# SCH_Piano_12_keys_2022-07-06.net
KiCad netlist of a schematic drawn in EasyEDA
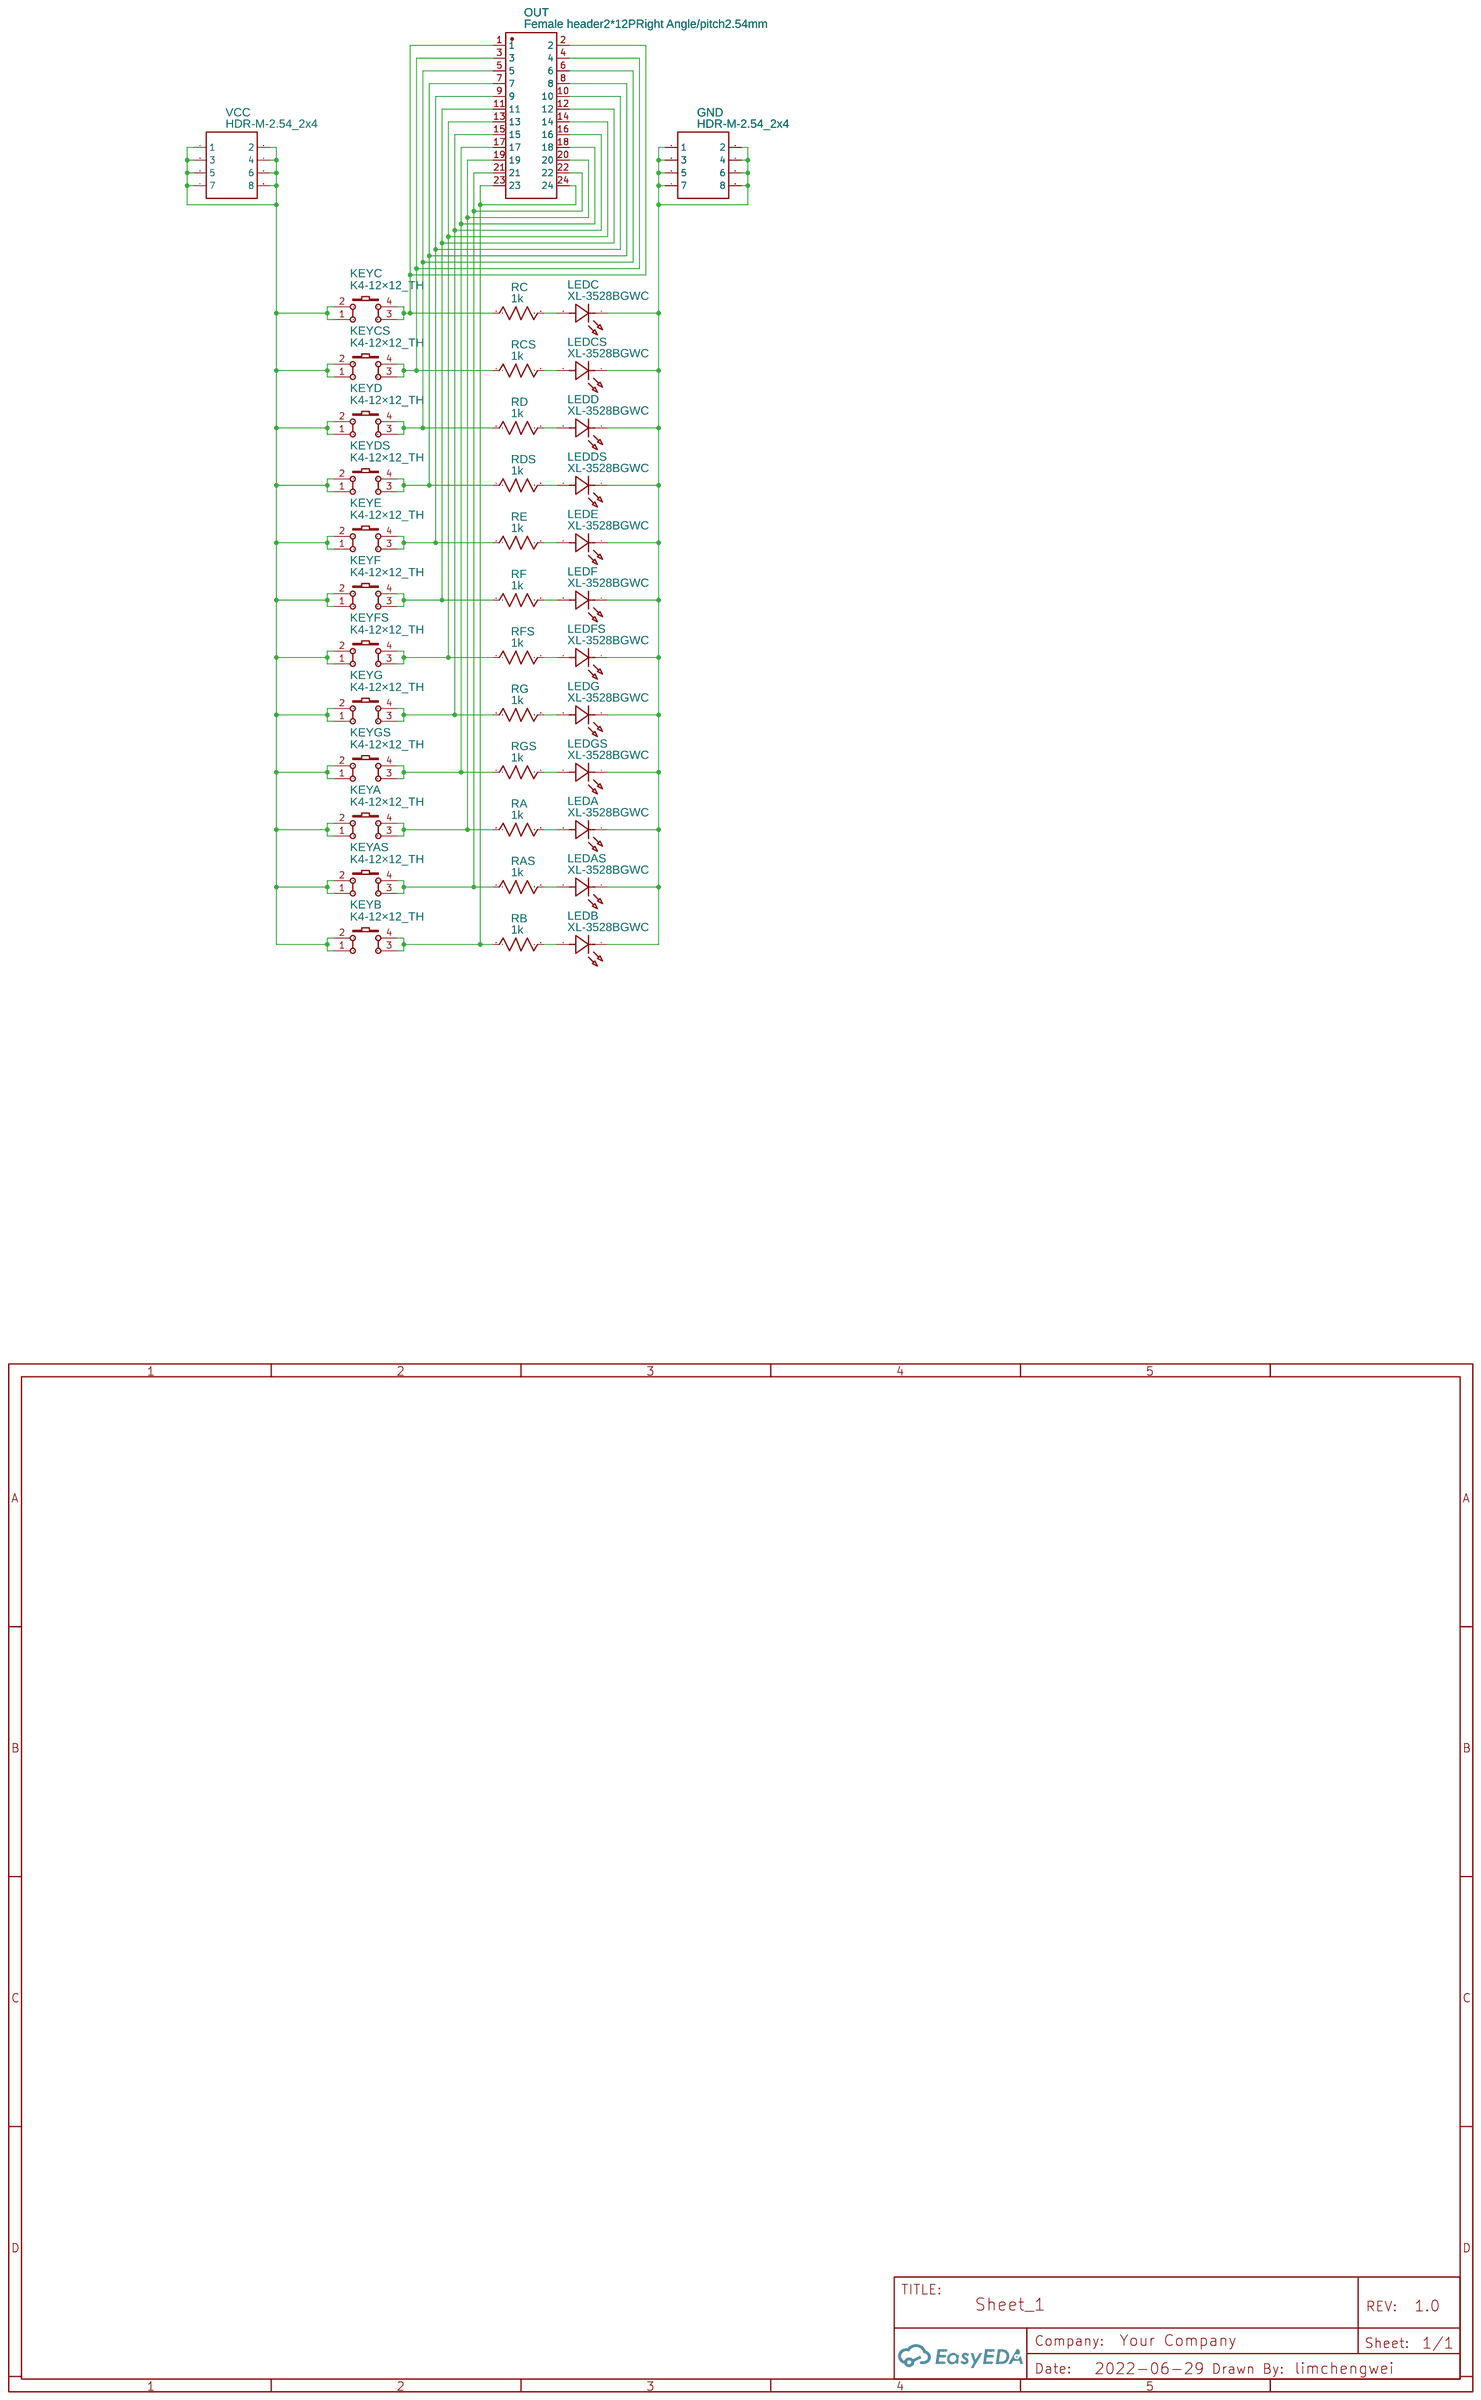
[diagram p0: schematic sheet]

(export (version "E")
  (design (tool "Eeschema 10.0.6"))
  (components
    (comp (ref "GND")
      (value "HDR-M-2.54_2x4")
      (fields (field (name "BOM_Supplier Part") "C58363"))
      (libsource (lib "") (part "HDR-M-2.54_2x4"))
    )
    (comp (ref "KEYA")
      (value "K4-12×12_TH")
      (fields
        (field (name "BOM_Manufacturer Part") "K2-1103DP-M4SW-04")
        (field (name "BOM_Supplier Part") "C128053")
      )
      (libsource (lib "") (part "K4-12×12_TH_9"))
    )
    (comp (ref "KEYAS")
      (value "K4-12×12_TH")
      (fields
        (field (name "BOM_Manufacturer Part") "K2-1103DP-M4SW-04")
        (field (name "BOM_Supplier Part") "C128053")
      )
      (libsource (lib "") (part "K4-12×12_TH_10"))
    )
    (comp (ref "KEYB")
      (value "K4-12×12_TH")
      (fields
        (field (name "BOM_Manufacturer Part") "K2-1103DP-M4SW-04")
        (field (name "BOM_Supplier Part") "C128053")
      )
      (libsource (lib "") (part "K4-12×12_TH_4"))
    )
    (comp (ref "KEYC")
      (value "K4-12×12_TH")
      (fields
        (field (name "BOM_Manufacturer Part") "K2-1103DP-M4SW-04")
        (field (name "BOM_Supplier Part") "C128053")
      )
      (libsource (lib "") (part "K4-12×12_TH_3"))
    )
    (comp (ref "KEYCS")
      (value "K4-12×12_TH")
      (fields
        (field (name "BOM_Manufacturer Part") "K2-1103DP-M4SW-04")
        (field (name "BOM_Supplier Part") "C128053")
      )
      (libsource (lib "") (part "K4-12×12_TH"))
    )
    (comp (ref "KEYD")
      (value "K4-12×12_TH")
      (fields
        (field (name "BOM_Manufacturer Part") "K2-1103DP-M4SW-04")
        (field (name "BOM_Supplier Part") "C128053")
      )
      (libsource (lib "") (part "K4-12×12_TH_8"))
    )
    (comp (ref "KEYDS")
      (value "K4-12×12_TH")
      (fields
        (field (name "BOM_Manufacturer Part") "K2-1103DP-M4SW-04")
        (field (name "BOM_Supplier Part") "C128053")
      )
      (libsource (lib "") (part "K4-12×12_TH_1"))
    )
    (comp (ref "KEYE")
      (value "K4-12×12_TH")
      (fields
        (field (name "BOM_Manufacturer Part") "K2-1103DP-M4SW-04")
        (field (name "BOM_Supplier Part") "C128053")
      )
      (libsource (lib "") (part "K4-12×12_TH_11"))
    )
    (comp (ref "KEYF")
      (value "K4-12×12_TH")
      (fields
        (field (name "BOM_Manufacturer Part") "K2-1103DP-M4SW-04")
        (field (name "BOM_Supplier Part") "C128053")
      )
      (libsource (lib "") (part "K4-12×12_TH_6"))
    )
    (comp (ref "KEYFS")
      (value "K4-12×12_TH")
      (fields
        (field (name "BOM_Manufacturer Part") "K2-1103DP-M4SW-04")
        (field (name "BOM_Supplier Part") "C128053")
      )
      (libsource (lib "") (part "K4-12×12_TH_2"))
    )
    (comp (ref "KEYG")
      (value "K4-12×12_TH")
      (fields
        (field (name "BOM_Manufacturer Part") "K2-1103DP-M4SW-04")
        (field (name "BOM_Supplier Part") "C128053")
      )
      (libsource (lib "") (part "K4-12×12_TH_7"))
    )
    (comp (ref "KEYGS")
      (value "K4-12×12_TH")
      (fields
        (field (name "BOM_Manufacturer Part") "K2-1103DP-M4SW-04")
        (field (name "BOM_Supplier Part") "C128053")
      )
      (libsource (lib "") (part "K4-12×12_TH_5"))
    )
    (comp (ref "LEDA")
      (value "XL-3528BGWC")
      (fields (field (name "BOM_Supplier Part") "C2843807"))
      (libsource (lib "") (part "XL-3528BGWC_7"))
    )
    (comp (ref "LEDAS")
      (value "XL-3528BGWC")
      (fields (field (name "BOM_Supplier Part") "C2843807"))
      (libsource (lib "") (part "XL-3528BGWC_1"))
    )
    (comp (ref "LEDB")
      (value "XL-3528BGWC")
      (fields (field (name "BOM_Supplier Part") "C2843807"))
      (libsource (lib "") (part "XL-3528BGWC"))
    )
    (comp (ref "LEDC")
      (value "XL-3528BGWC")
      (fields (field (name "BOM_Supplier Part") "C2843807"))
      (libsource (lib "") (part "XL-3528BGWC_5"))
    )
    (comp (ref "LEDCS")
      (value "XL-3528BGWC")
      (fields (field (name "BOM_Supplier Part") "C2843807"))
      (libsource (lib "") (part "XL-3528BGWC_11"))
    )
    (comp (ref "LEDD")
      (value "XL-3528BGWC")
      (fields (field (name "BOM_Supplier Part") "C2843807"))
      (libsource (lib "") (part "XL-3528BGWC_8"))
    )
    (comp (ref "LEDDS")
      (value "XL-3528BGWC")
      (fields (field (name "BOM_Supplier Part") "C2843807"))
      (libsource (lib "") (part "XL-3528BGWC_9"))
    )
    (comp (ref "LEDE")
      (value "XL-3528BGWC")
      (fields (field (name "BOM_Supplier Part") "C2843807"))
      (libsource (lib "") (part "XL-3528BGWC_2"))
    )
    (comp (ref "LEDF")
      (value "XL-3528BGWC")
      (fields (field (name "BOM_Supplier Part") "C2843807"))
      (libsource (lib "") (part "XL-3528BGWC_6"))
    )
    (comp (ref "LEDFS")
      (value "XL-3528BGWC")
      (fields (field (name "BOM_Supplier Part") "C2843807"))
      (libsource (lib "") (part "XL-3528BGWC_4"))
    )
    (comp (ref "LEDG")
      (value "XL-3528BGWC")
      (fields (field (name "BOM_Supplier Part") "C2843807"))
      (libsource (lib "") (part "XL-3528BGWC_3"))
    )
    (comp (ref "LEDGS")
      (value "XL-3528BGWC")
      (fields (field (name "BOM_Supplier Part") "C2843807"))
      (libsource (lib "") (part "XL-3528BGWC_10"))
    )
    (comp (ref "OUT")
      (value "Female header2*12PRight Angle/pitch2.54mm")
      (fields (field (name "BOM_Supplier Part") "C62744"))
      (libsource (lib "") (part "Female header2*12PRight Angle/pitch2.54mm"))
    )
    (comp (ref "RA") (value "1k") (libsource (lib "") (part "R_1206_US_8")))
    (comp (ref "RAS") (value "1k") (libsource (lib "") (part "R_1206_US_6")))
    (comp (ref "RB") (value "1k") (libsource (lib "") (part "R_1206_US_4")))
    (comp (ref "RC") (value "1k") (libsource (lib "") (part "R_1206_US_3")))
    (comp (ref "RCS") (value "1k") (libsource (lib "") (part "R_1206_US_1")))
    (comp (ref "RD") (value "1k") (libsource (lib "") (part "R_1206_US_2")))
    (comp (ref "RDS") (value "1k") (libsource (lib "") (part "R_1206_US_9")))
    (comp (ref "RE") (value "1k") (libsource (lib "") (part "R_1206_US_11")))
    (comp (ref "RF") (value "1k") (libsource (lib "") (part "R_1206_US")))
    (comp (ref "RFS") (value "1k") (libsource (lib "") (part "R_1206_US_5")))
    (comp (ref "RG") (value "1k") (libsource (lib "") (part "R_1206_US_10")))
    (comp (ref "RGS") (value "1k") (libsource (lib "") (part "R_1206_US_7")))
    (comp (ref "VCC")
      (value "HDR-M-2.54_2x4")
      (fields (field (name "BOM_Supplier Part") "C58363"))
      (libsource (lib "") (part "HDR-M-2.54_2x4_1"))
    )
  )
  (nets
    (net (code "1") (name "Net-(KEYA-Pad1)") (class "Default")
      (node (ref "KEYA") (pin "1") (pinfunction "1_1") (pintype "unspecified"))
      (node (ref "KEYA") (pin "2") (pinfunction "2_2") (pintype "unspecified"))
      (node (ref "KEYAS") (pin "1") (pinfunction "1_1") (pintype "unspecified"))
      (node (ref "KEYAS") (pin "2") (pinfunction "2_2") (pintype "unspecified"))
      (node (ref "KEYB") (pin "1") (pinfunction "1_1") (pintype "unspecified"))
      (node (ref "KEYB") (pin "2") (pinfunction "2_2") (pintype "unspecified"))
      (node (ref "KEYC") (pin "1") (pinfunction "1_1") (pintype "unspecified"))
      (node (ref "KEYC") (pin "2") (pinfunction "2_2") (pintype "unspecified"))
      (node (ref "KEYCS") (pin "1") (pinfunction "1_1") (pintype "unspecified"))
      (node (ref "KEYCS") (pin "2") (pinfunction "2_2") (pintype "unspecified"))
      (node (ref "KEYD") (pin "1") (pinfunction "1_1") (pintype "unspecified"))
      (node (ref "KEYD") (pin "2") (pinfunction "2_2") (pintype "unspecified"))
      (node (ref "KEYDS") (pin "1") (pinfunction "1_1") (pintype "unspecified"))
      (node (ref "KEYDS") (pin "2") (pinfunction "2_2") (pintype "unspecified"))
      (node (ref "KEYE") (pin "1") (pinfunction "1_1") (pintype "unspecified"))
      (node (ref "KEYE") (pin "2") (pinfunction "2_2") (pintype "unspecified"))
      (node (ref "KEYF") (pin "1") (pinfunction "1_1") (pintype "unspecified"))
      (node (ref "KEYF") (pin "2") (pinfunction "2_2") (pintype "unspecified"))
      (node (ref "KEYFS") (pin "1") (pinfunction "1_1") (pintype "unspecified"))
      (node (ref "KEYFS") (pin "2") (pinfunction "2_2") (pintype "unspecified"))
      (node (ref "KEYG") (pin "1") (pinfunction "1_1") (pintype "unspecified"))
      (node (ref "KEYG") (pin "2") (pinfunction "2_2") (pintype "unspecified"))
      (node (ref "KEYGS") (pin "1") (pinfunction "1_1") (pintype "unspecified"))
      (node (ref "KEYGS") (pin "2") (pinfunction "2_2") (pintype "unspecified"))
      (node (ref "VCC") (pin "1") (pinfunction "1_1") (pintype "unspecified"))
      (node (ref "VCC") (pin "2") (pinfunction "2_2") (pintype "unspecified"))
      (node (ref "VCC") (pin "3") (pinfunction "3_3") (pintype "unspecified"))
      (node (ref "VCC") (pin "4") (pinfunction "4_4") (pintype "unspecified"))
      (node (ref "VCC") (pin "5") (pinfunction "5_5") (pintype "unspecified"))
      (node (ref "VCC") (pin "6") (pinfunction "6_6") (pintype "unspecified"))
      (node (ref "VCC") (pin "7") (pinfunction "7_7") (pintype "unspecified"))
      (node (ref "VCC") (pin "8") (pinfunction "8_8") (pintype "unspecified"))
    )
    (net (code "2") (name "Net-(KEYA-Pad3)") (class "Default")
      (node (ref "KEYA") (pin "3") (pinfunction "3_3") (pintype "unspecified"))
      (node (ref "KEYA") (pin "4") (pinfunction "4_4") (pintype "unspecified"))
      (node (ref "OUT") (pin "19") (pinfunction "19_19") (pintype "unspecified"))
      (node (ref "OUT") (pin "20") (pinfunction "20_20") (pintype "unspecified"))
      (node (ref "RA") (pin "1") (pinfunction "1_1") (pintype "unspecified"))
    )
    (net (code "3") (name "Net-(KEYAS-Pad3)") (class "Default")
      (node (ref "KEYAS") (pin "3") (pinfunction "3_3") (pintype "unspecified"))
      (node (ref "KEYAS") (pin "4") (pinfunction "4_4") (pintype "unspecified"))
      (node (ref "OUT") (pin "21") (pinfunction "21_21") (pintype "unspecified"))
      (node (ref "OUT") (pin "22") (pinfunction "22_22") (pintype "unspecified"))
      (node (ref "RAS") (pin "1") (pinfunction "1_1") (pintype "unspecified"))
    )
    (net (code "4") (name "Net-(KEYB-Pad3)") (class "Default")
      (node (ref "KEYB") (pin "3") (pinfunction "3_3") (pintype "unspecified"))
      (node (ref "KEYB") (pin "4") (pinfunction "4_4") (pintype "unspecified"))
      (node (ref "OUT") (pin "23") (pinfunction "23_23") (pintype "unspecified"))
      (node (ref "OUT") (pin "24") (pinfunction "24_24") (pintype "unspecified"))
      (node (ref "RB") (pin "1") (pinfunction "1_1") (pintype "unspecified"))
    )
    (net (code "5") (name "Net-(KEYC-Pad3)") (class "Default")
      (node (ref "KEYC") (pin "3") (pinfunction "3_3") (pintype "unspecified"))
      (node (ref "KEYC") (pin "4") (pinfunction "4_4") (pintype "unspecified"))
      (node (ref "OUT") (pin "1") (pinfunction "1_1") (pintype "unspecified"))
      (node (ref "OUT") (pin "2") (pinfunction "2_2") (pintype "unspecified"))
      (node (ref "RC") (pin "1") (pinfunction "1_1") (pintype "unspecified"))
    )
    (net (code "6") (name "Net-(KEYCS-Pad3)") (class "Default")
      (node (ref "KEYCS") (pin "3") (pinfunction "3_3") (pintype "unspecified"))
      (node (ref "KEYCS") (pin "4") (pinfunction "4_4") (pintype "unspecified"))
      (node (ref "OUT") (pin "3") (pinfunction "3_3") (pintype "unspecified"))
      (node (ref "OUT") (pin "4") (pinfunction "4_4") (pintype "unspecified"))
      (node (ref "RCS") (pin "1") (pinfunction "1_1") (pintype "unspecified"))
    )
    (net (code "7") (name "Net-(KEYD-Pad3)") (class "Default")
      (node (ref "KEYD") (pin "3") (pinfunction "3_3") (pintype "unspecified"))
      (node (ref "KEYD") (pin "4") (pinfunction "4_4") (pintype "unspecified"))
      (node (ref "OUT") (pin "5") (pinfunction "5_5") (pintype "unspecified"))
      (node (ref "OUT") (pin "6") (pinfunction "6_6") (pintype "unspecified"))
      (node (ref "RD") (pin "1") (pinfunction "1_1") (pintype "unspecified"))
    )
    (net (code "8") (name "Net-(KEYDS-Pad3)") (class "Default")
      (node (ref "KEYDS") (pin "3") (pinfunction "3_3") (pintype "unspecified"))
      (node (ref "KEYDS") (pin "4") (pinfunction "4_4") (pintype "unspecified"))
      (node (ref "OUT") (pin "7") (pinfunction "7_7") (pintype "unspecified"))
      (node (ref "OUT") (pin "8") (pinfunction "8_8") (pintype "unspecified"))
      (node (ref "RDS") (pin "1") (pinfunction "1_1") (pintype "unspecified"))
    )
    (net (code "9") (name "Net-(KEYE-Pad3)") (class "Default")
      (node (ref "KEYE") (pin "3") (pinfunction "3_3") (pintype "unspecified"))
      (node (ref "KEYE") (pin "4") (pinfunction "4_4") (pintype "unspecified"))
      (node (ref "OUT") (pin "10") (pinfunction "10_10") (pintype "unspecified"))
      (node (ref "OUT") (pin "9") (pinfunction "9_9") (pintype "unspecified"))
      (node (ref "RE") (pin "1") (pinfunction "1_1") (pintype "unspecified"))
    )
    (net (code "10") (name "Net-(KEYF-Pad3)") (class "Default")
      (node (ref "KEYF") (pin "3") (pinfunction "3_3") (pintype "unspecified"))
      (node (ref "KEYF") (pin "4") (pinfunction "4_4") (pintype "unspecified"))
      (node (ref "OUT") (pin "11") (pinfunction "11_11") (pintype "unspecified"))
      (node (ref "OUT") (pin "12") (pinfunction "12_12") (pintype "unspecified"))
      (node (ref "RF") (pin "1") (pinfunction "1_1") (pintype "unspecified"))
    )
    (net (code "11") (name "Net-(KEYFS-Pad3)") (class "Default")
      (node (ref "KEYFS") (pin "3") (pinfunction "3_3") (pintype "unspecified"))
      (node (ref "KEYFS") (pin "4") (pinfunction "4_4") (pintype "unspecified"))
      (node (ref "OUT") (pin "13") (pinfunction "13_13") (pintype "unspecified"))
      (node (ref "OUT") (pin "14") (pinfunction "14_14") (pintype "unspecified"))
      (node (ref "RFS") (pin "1") (pinfunction "1_1") (pintype "unspecified"))
    )
    (net (code "12") (name "Net-(KEYG-Pad3)") (class "Default")
      (node (ref "KEYG") (pin "3") (pinfunction "3_3") (pintype "unspecified"))
      (node (ref "KEYG") (pin "4") (pinfunction "4_4") (pintype "unspecified"))
      (node (ref "OUT") (pin "15") (pinfunction "15_15") (pintype "unspecified"))
      (node (ref "OUT") (pin "16") (pinfunction "16_16") (pintype "unspecified"))
      (node (ref "RG") (pin "1") (pinfunction "1_1") (pintype "unspecified"))
    )
    (net (code "13") (name "Net-(KEYGS-Pad3)") (class "Default")
      (node (ref "KEYGS") (pin "3") (pinfunction "3_3") (pintype "unspecified"))
      (node (ref "KEYGS") (pin "4") (pinfunction "4_4") (pintype "unspecified"))
      (node (ref "OUT") (pin "17") (pinfunction "17_17") (pintype "unspecified"))
      (node (ref "OUT") (pin "18") (pinfunction "18_18") (pintype "unspecified"))
      (node (ref "RGS") (pin "1") (pinfunction "1_1") (pintype "unspecified"))
    )
    (net (code "14") (name "Net-(LEDA-A)") (class "Default")
      (node (ref "LEDA") (pin "2") (pinfunction "A_2") (pintype "unspecified"))
      (node (ref "RA") (pin "2") (pinfunction "2_2") (pintype "unspecified"))
    )
    (net (code "15") (name "Net-(LEDA-K)") (class "Default")
      (node (ref "GND") (pin "1") (pinfunction "1_1") (pintype "unspecified"))
      (node (ref "GND") (pin "2") (pinfunction "2_2") (pintype "unspecified"))
      (node (ref "GND") (pin "3") (pinfunction "3_3") (pintype "unspecified"))
      (node (ref "GND") (pin "4") (pinfunction "4_4") (pintype "unspecified"))
      (node (ref "GND") (pin "5") (pinfunction "5_5") (pintype "unspecified"))
      (node (ref "GND") (pin "6") (pinfunction "6_6") (pintype "unspecified"))
      (node (ref "GND") (pin "7") (pinfunction "7_7") (pintype "unspecified"))
      (node (ref "GND") (pin "8") (pinfunction "8_8") (pintype "unspecified"))
      (node (ref "LEDA") (pin "1") (pinfunction "K_1") (pintype "unspecified"))
      (node (ref "LEDAS") (pin "1") (pinfunction "K_1") (pintype "unspecified"))
      (node (ref "LEDB") (pin "1") (pinfunction "K_1") (pintype "unspecified"))
      (node (ref "LEDC") (pin "1") (pinfunction "K_1") (pintype "unspecified"))
      (node (ref "LEDCS") (pin "1") (pinfunction "K_1") (pintype "unspecified"))
      (node (ref "LEDD") (pin "1") (pinfunction "K_1") (pintype "unspecified"))
      (node (ref "LEDDS") (pin "1") (pinfunction "K_1") (pintype "unspecified"))
      (node (ref "LEDE") (pin "1") (pinfunction "K_1") (pintype "unspecified"))
      (node (ref "LEDF") (pin "1") (pinfunction "K_1") (pintype "unspecified"))
      (node (ref "LEDFS") (pin "1") (pinfunction "K_1") (pintype "unspecified"))
      (node (ref "LEDG") (pin "1") (pinfunction "K_1") (pintype "unspecified"))
      (node (ref "LEDGS") (pin "1") (pinfunction "K_1") (pintype "unspecified"))
    )
    (net (code "16") (name "Net-(LEDAS-A)") (class "Default")
      (node (ref "LEDAS") (pin "2") (pinfunction "A_2") (pintype "unspecified"))
      (node (ref "RAS") (pin "2") (pinfunction "2_2") (pintype "unspecified"))
    )
    (net (code "17") (name "Net-(LEDB-A)") (class "Default")
      (node (ref "LEDB") (pin "2") (pinfunction "A_2") (pintype "unspecified"))
      (node (ref "RB") (pin "2") (pinfunction "2_2") (pintype "unspecified"))
    )
    (net (code "18") (name "Net-(LEDC-A)") (class "Default")
      (node (ref "LEDC") (pin "2") (pinfunction "A_2") (pintype "unspecified"))
      (node (ref "RC") (pin "2") (pinfunction "2_2") (pintype "unspecified"))
    )
    (net (code "19") (name "Net-(LEDCS-A)") (class "Default")
      (node (ref "LEDCS") (pin "2") (pinfunction "A_2") (pintype "unspecified"))
      (node (ref "RCS") (pin "2") (pinfunction "2_2") (pintype "unspecified"))
    )
    (net (code "20") (name "Net-(LEDD-A)") (class "Default")
      (node (ref "LEDD") (pin "2") (pinfunction "A_2") (pintype "unspecified"))
      (node (ref "RD") (pin "2") (pinfunction "2_2") (pintype "unspecified"))
    )
    (net (code "21") (name "Net-(LEDDS-A)") (class "Default")
      (node (ref "LEDDS") (pin "2") (pinfunction "A_2") (pintype "unspecified"))
      (node (ref "RDS") (pin "2") (pinfunction "2_2") (pintype "unspecified"))
    )
    (net (code "22") (name "Net-(LEDE-A)") (class "Default")
      (node (ref "LEDE") (pin "2") (pinfunction "A_2") (pintype "unspecified"))
      (node (ref "RE") (pin "2") (pinfunction "2_2") (pintype "unspecified"))
    )
    (net (code "23") (name "Net-(LEDF-A)") (class "Default")
      (node (ref "LEDF") (pin "2") (pinfunction "A_2") (pintype "unspecified"))
      (node (ref "RF") (pin "2") (pinfunction "2_2") (pintype "unspecified"))
    )
    (net (code "24") (name "Net-(LEDFS-A)") (class "Default")
      (node (ref "LEDFS") (pin "2") (pinfunction "A_2") (pintype "unspecified"))
      (node (ref "RFS") (pin "2") (pinfunction "2_2") (pintype "unspecified"))
    )
    (net (code "25") (name "Net-(LEDG-A)") (class "Default")
      (node (ref "LEDG") (pin "2") (pinfunction "A_2") (pintype "unspecified"))
      (node (ref "RG") (pin "2") (pinfunction "2_2") (pintype "unspecified"))
    )
    (net (code "26") (name "Net-(LEDGS-A)") (class "Default")
      (node (ref "LEDGS") (pin "2") (pinfunction "A_2") (pintype "unspecified"))
      (node (ref "RGS") (pin "2") (pinfunction "2_2") (pintype "unspecified"))
    )
  )
)
